# ir_module.net
KiCad netlist of a schematic drawn in EAGLE
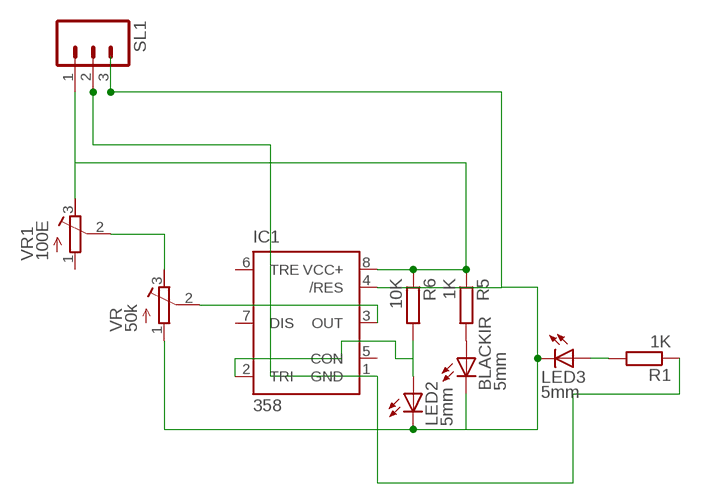
[diagram p0: schematic, sheet 1]

(export (version "E")
  (design (tool "Eeschema 10.0.6"))
  (components
    (comp (ref "BLACKIR")
      (value "5mm")
      (footprint "eagle-import:LED5MM")
      (libsource (lib "eagle-import") (part "LED5MM"))
    )
    (comp (ref "IC1")
      (value "358")
      (footprint "eagle-import:DIL-08")
      (fields (field (name "MF") "Arrow Electronics") (field (name "MPN") "NE555N"))
      (libsource (lib "eagle-import") (part "NE555"))
    )
    (comp (ref "LED2")
      (value "5mm")
      (footprint "eagle-import:LED5MM")
      (libsource (lib "eagle-import") (part "LED5MM"))
    )
    (comp (ref "LED3")
      (value "5mm")
      (footprint "eagle-import:LED5MM")
      (libsource (lib "eagle-import") (part "LED5MM"))
    )
    (comp (ref "R1")
      (value "1K")
      (footprint "eagle-import:0204_7")
      (libsource (lib "eagle-import") (part "R-EU_0204/7"))
    )
    (comp (ref "R5")
      (value "1K")
      (footprint "eagle-import:0204_7")
      (libsource (lib "eagle-import") (part "R-EU_0204/7"))
    )
    (comp (ref "R6")
      (value "10K")
      (footprint "eagle-import:0204_7")
      (libsource (lib "eagle-import") (part "R-EU_0204/7"))
    )
    (comp (ref "SL1")
      (value "M03")
      (footprint "eagle-import:03P")
      (libsource (lib "eagle-import") (part "M03"))
    )
    (comp (ref "VR")
      (value "50k")
      (footprint "eagle-import:RTRIM64P")
      (libsource (lib "eagle-import") (part "R-TRIMM64P"))
    )
    (comp (ref "VR1")
      (value "100E")
      (footprint "eagle-import:RTRIM64P")
      (libsource (lib "eagle-import") (part "R-TRIMM64P"))
    )
  )
  (nets
    (net (code "1") (name "Net-(BLACKIR-C)") (class "Default")
      (node (ref "BLACKIR") (pin "K") (pinfunction "C_K") (pintype "passive"))
      (node (ref "IC1") (pin "4") (pinfunction "/RES_4") (pintype "input"))
      (node (ref "LED2") (pin "K") (pinfunction "C_K") (pintype "passive"))
      (node (ref "LED3") (pin "K") (pinfunction "C_K") (pintype "passive"))
      (node (ref "SL1") (pin "3") (pinfunction "3_3") (pintype "passive"))
      (node (ref "VR") (pin "1") (pinfunction "E_1") (pintype "passive"))
    )
    (net (code "2") (name "Net-(BLACKIR-PadA)") (class "Default")
      (node (ref "BLACKIR") (pin "A") (pinfunction "A_A") (pintype "passive"))
      (node (ref "R5") (pin "2") (pinfunction "2_2") (pintype "passive"))
    )
    (net (code "3") (name "Net-(IC1-GND)") (class "Default")
      (node (ref "IC1") (pin "1") (pinfunction "GND_1") (pintype "power_in"))
      (node (ref "R1") (pin "1") (pinfunction "1_1") (pintype "passive"))
      (node (ref "SL1") (pin "2") (pinfunction "2_2") (pintype "passive"))
    )
    (net (code "4") (name "Net-(IC1-OUT)") (class "Default")
      (node (ref "IC1") (pin "3") (pinfunction "OUT_3") (pintype "output"))
      (node (ref "VR") (pin "2") (pinfunction "S_2") (pintype "passive"))
    )
    (net (code "5") (name "Net-(IC1-TRI)") (class "Default")
      (node (ref "IC1") (pin "2") (pinfunction "TRI_2") (pintype "input"))
      (node (ref "LED2") (pin "A") (pinfunction "A_A") (pintype "passive"))
      (node (ref "R6") (pin "2") (pinfunction "2_2") (pintype "passive"))
    )
    (net (code "6") (name "Net-(IC1-VCC+)") (class "Default")
      (node (ref "IC1") (pin "8") (pinfunction "VCC+_8") (pintype "power_in"))
      (node (ref "R5") (pin "1") (pinfunction "1_1") (pintype "passive"))
      (node (ref "R6") (pin "1") (pinfunction "1_1") (pintype "passive"))
      (node (ref "SL1") (pin "1") (pinfunction "1_1") (pintype "passive"))
      (node (ref "VR1") (pin "3") (pinfunction "A_3") (pintype "passive"))
    )
    (net (code "7") (name "Net-(LED3-PadA)") (class "Default")
      (node (ref "LED3") (pin "A") (pinfunction "A_A") (pintype "passive"))
      (node (ref "R1") (pin "2") (pinfunction "2_2") (pintype "passive"))
    )
    (net (code "8") (name "Net-(VR-A)") (class "Default")
      (node (ref "VR") (pin "3") (pinfunction "A_3") (pintype "passive"))
      (node (ref "VR1") (pin "2") (pinfunction "S_2") (pintype "passive"))
    )
    (net (code "9") (name "unconnected-(IC1-CON-Pad5)") (class "Default")
      (node (ref "IC1") (pin "5") (pinfunction "CON_5") (pintype "input"))
    )
    (net (code "10") (name "unconnected-(IC1-DIS-Pad7)") (class "Default")
      (node (ref "IC1") (pin "7") (pinfunction "DIS_7") (pintype "input"))
    )
    (net (code "11") (name "unconnected-(IC1-TRE-Pad6)") (class "Default")
      (node (ref "IC1") (pin "6") (pinfunction "TRE_6") (pintype "input"))
    )
    (net (code "12") (name "unconnected-(VR1-E-Pad1)") (class "Default")
      (node (ref "VR1") (pin "1") (pinfunction "E_1") (pintype "passive"))
    )
  )
)
